# msp430_funky.net
KiCad netlist of a schematic drawn in EAGLE
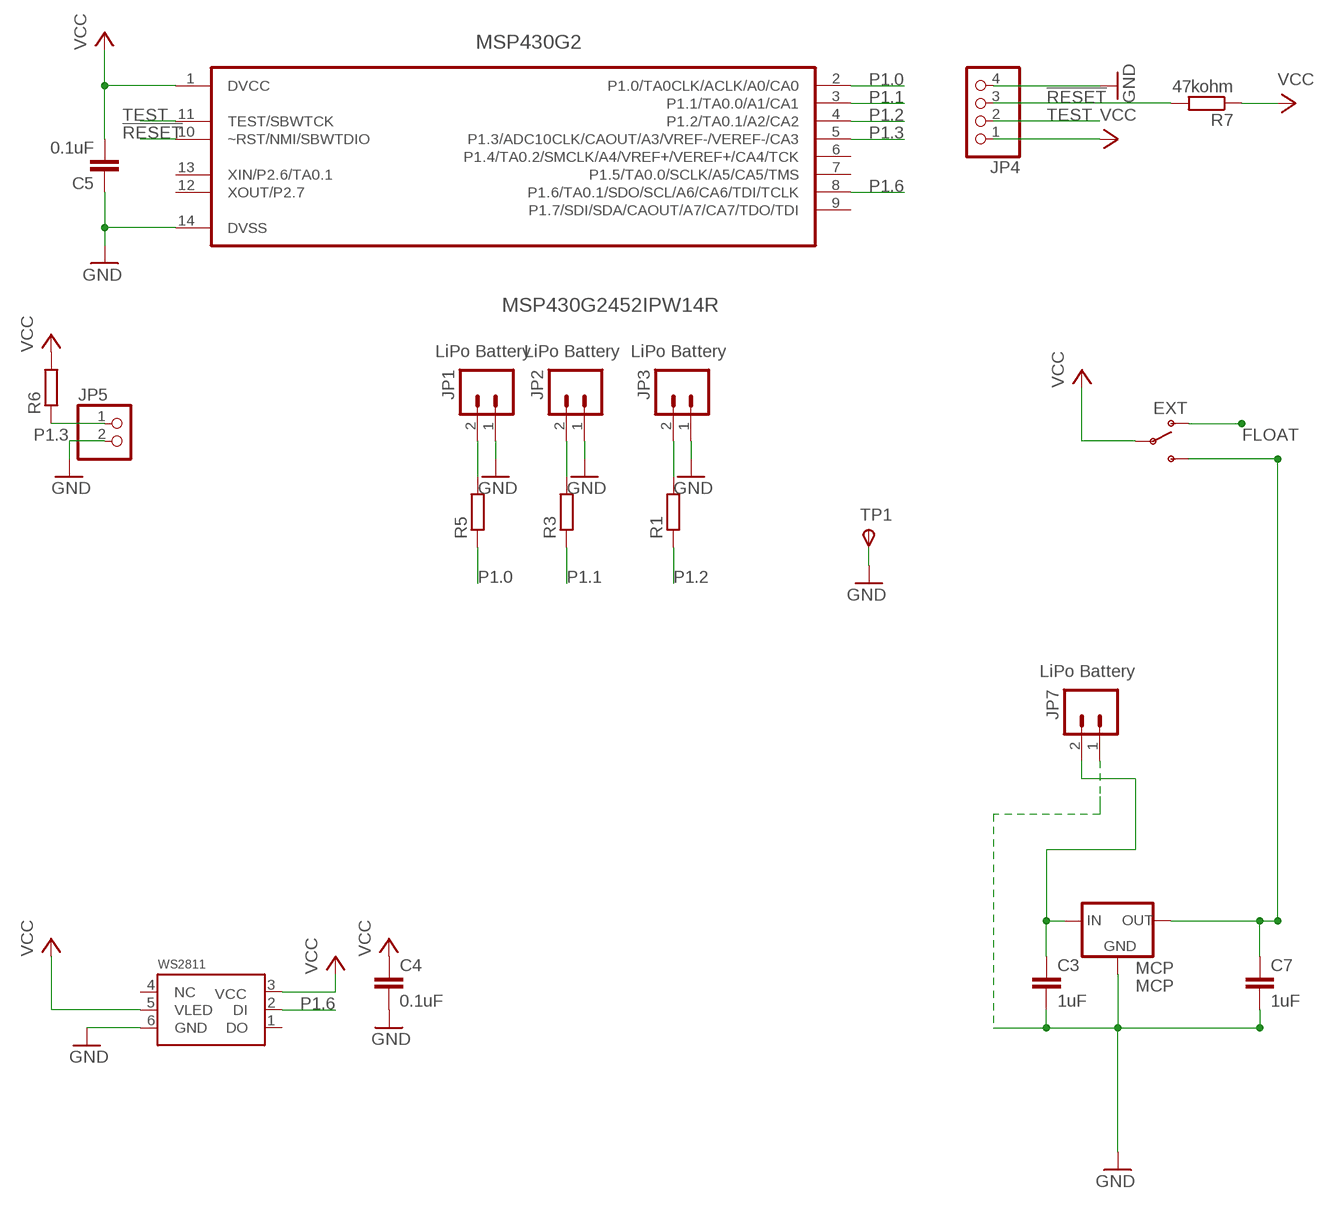
[diagram p0: schematic, sheet 1]

(export (version "E")
  (design (tool "Eeschema 10.0.6"))
  (components
    (comp (ref "C3")
      (value "1uF")
      (footprint "eagle-import:C0805")
      (libsource (lib "eagle-import") (part "C-EUC0805"))
    )
    (comp (ref "C4")
      (value "0.1uF")
      (footprint "eagle-import:C0805")
      (libsource (lib "eagle-import") (part "C-EUC0805"))
    )
    (comp (ref "C5")
      (value "0.1uF")
      (footprint "eagle-import:C0805")
      (libsource (lib "eagle-import") (part "C-EUC0805"))
    )
    (comp (ref "C7")
      (value "1uF")
      (footprint "eagle-import:C0805")
      (libsource (lib "eagle-import") (part "C-EUC0805"))
    )
    (comp (ref "JP1")
      (value "LiPo Battery")
      (footprint "eagle-import:JST-2-PTH")
      (libsource (lib "eagle-import") (part "M02JST-PTH-2"))
    )
    (comp (ref "JP2")
      (value "LiPo Battery")
      (footprint "eagle-import:JST-2-PTH")
      (libsource (lib "eagle-import") (part "M02JST-PTH-2"))
    )
    (comp (ref "JP3")
      (value "LiPo Battery")
      (footprint "eagle-import:JST-2-PTH")
      (libsource (lib "eagle-import") (part "M02JST-PTH-2"))
    )
    (comp (ref "JP4")
      (value "PINHD-1X4")
      (footprint "eagle-import:1X04")
      (libsource (lib "eagle-import") (part "PINHD-1X4"))
    )
    (comp (ref "JP5")
      (value "PINHD-1X2")
      (footprint "eagle-import:1X02")
      (libsource (lib "eagle-import") (part "PINHD-1X2"))
    )
    (comp (ref "JP7")
      (value "LiPo Battery")
      (footprint "eagle-import:JST-2-PTH")
      (libsource (lib "eagle-import") (part "M02JST-PTH-2"))
    )
    (comp (ref "MCP")
      (value "MCP")
      (footprint "eagle-import:SOT-23")
      (libsource (lib "eagle-import") (part "MCP1700SOT-23"))
    )
    (comp (ref "MSP430G2")
      (value "MSP430G2452IPW14R")
      (footprint "eagle-import:SOP65P640X120-14N")
      (libsource (lib "eagle-import") (part "MSP430G2452IPW14R"))
    )
    (comp (ref "ON")
      (value "EXT")
      (footprint "eagle-import:SWITCH-SPDT")
      (libsource (lib "eagle-import") (part "SWITCH-SPSTPTH"))
    )
    (comp (ref "R1")
      (value "R-EU_R0805")
      (footprint "eagle-import:R0805")
      (libsource (lib "eagle-import") (part "R-EU_R0805"))
    )
    (comp (ref "R3")
      (value "R-EU_R0805")
      (footprint "eagle-import:R0805")
      (libsource (lib "eagle-import") (part "R-EU_R0805"))
    )
    (comp (ref "R5")
      (value "R-EU_R0805")
      (footprint "eagle-import:R0805")
      (libsource (lib "eagle-import") (part "R-EU_R0805"))
    )
    (comp (ref "R6")
      (value "R-EU_R0805")
      (footprint "eagle-import:R0805")
      (libsource (lib "eagle-import") (part "R-EU_R0805"))
    )
    (comp (ref "R7")
      (value "47kohm")
      (footprint "eagle-import:R0805")
      (libsource (lib "eagle-import") (part "R-EU_R0805"))
    )
    (comp (ref "TP1")
      (value "TPSTP20R")
      (footprint "eagle-import:TP20R")
      (libsource (lib "eagle-import") (part "TPSTP20R"))
    )
    (comp (ref "WS2811")
      (value "5050WS2811W")
      (footprint "eagle-import:RGBLED5050W")
      (libsource (lib "eagle-import") (part "5050WS2811W"))
    )
  )
  (nets
    (net (code "1") (name "/FLOAT") (class "Default")
      (node (ref "ON") (pin "1") (pinfunction "O_1") (pintype "passive"))
    )
    (net (code "2") (name "/P1.0") (class "Default")
      (node (ref "MSP430G2") (pin "2") (pinfunction "P1.0/TA0CLK/ACLK/A0/CA0_2") (pintype "bidirectional"))
      (node (ref "R5") (pin "1") (pinfunction "1_1") (pintype "passive"))
    )
    (net (code "3") (name "/P1.1") (class "Default")
      (node (ref "MSP430G2") (pin "3") (pinfunction "P1.1/TA0.0/A1/CA1_3") (pintype "bidirectional"))
      (node (ref "R3") (pin "1") (pinfunction "1_1") (pintype "passive"))
    )
    (net (code "4") (name "/P1.2") (class "Default")
      (node (ref "MSP430G2") (pin "4") (pinfunction "P1.2/TA0.1/A2/CA2_4") (pintype "bidirectional"))
      (node (ref "R1") (pin "1") (pinfunction "1_1") (pintype "passive"))
    )
    (net (code "5") (name "/P1.3") (class "Default")
      (node (ref "JP5") (pin "1") (pinfunction "1_1") (pintype "passive"))
      (node (ref "MSP430G2") (pin "5") (pinfunction "P1.3/ADC10CLK/CAOUT/A3/VREF-/VEREF-/CA3_5") (pintype "bidirectional"))
      (node (ref "R6") (pin "1") (pinfunction "1_1") (pintype "passive"))
    )
    (net (code "6") (name "/P1.6") (class "Default")
      (node (ref "MSP430G2") (pin "8") (pinfunction "P1.6/TA0.1/SDO/SCL/A6/CA6/TDI/TCLK_8") (pintype "bidirectional"))
      (node (ref "WS2811") (pin "2") (pinfunction "DI_2") (pintype "bidirectional"))
    )
    (net (code "7") (name "/TEST") (class "Default")
      (node (ref "JP4") (pin "2") (pinfunction "2_2") (pintype "passive"))
      (node (ref "MSP430G2") (pin "11") (pinfunction "TEST/SBWTCK_11") (pintype "input"))
    )
    (net (code "8") (name "/~{RESET}") (class "Default")
      (node (ref "JP4") (pin "3") (pinfunction "3_3") (pintype "passive"))
      (node (ref "MSP430G2") (pin "10") (pinfunction "~{RST/NMI/SBWTDIO}_10") (pintype "input"))
      (node (ref "R7") (pin "2") (pinfunction "2_2") (pintype "passive"))
    )
    (net (code "9") (name "GND") (class "Default")
      (node (ref "C3") (pin "2") (pinfunction "2_2") (pintype "passive"))
      (node (ref "C4") (pin "2") (pinfunction "2_2") (pintype "passive"))
      (node (ref "C5") (pin "1") (pinfunction "1_1") (pintype "passive"))
      (node (ref "C7") (pin "2") (pinfunction "2_2") (pintype "passive"))
      (node (ref "JP1") (pin "1") (pinfunction "1_1") (pintype "passive"))
      (node (ref "JP2") (pin "1") (pinfunction "1_1") (pintype "passive"))
      (node (ref "JP3") (pin "1") (pinfunction "1_1") (pintype "passive"))
      (node (ref "JP4") (pin "4") (pinfunction "4_4") (pintype "passive"))
      (node (ref "JP5") (pin "2") (pinfunction "2_2") (pintype "passive"))
      (node (ref "JP7") (pin "1") (pinfunction "1_1") (pintype "passive"))
      (node (ref "MCP") (pin "1") (pinfunction "GND_1") (pintype "input"))
      (node (ref "MSP430G2") (pin "14") (pinfunction "DVSS_14") (pintype "power_in"))
      (node (ref "TP1") (pin "TP") (pinfunction "PP_TP") (pintype "input"))
      (node (ref "WS2811") (pin "6") (pinfunction "GND_6") (pintype "bidirectional"))
    )
    (net (code "10") (name "Net-(JP1-Pad2)") (class "Default")
      (node (ref "JP1") (pin "2") (pinfunction "2_2") (pintype "passive"))
      (node (ref "R5") (pin "2") (pinfunction "2_2") (pintype "passive"))
    )
    (net (code "11") (name "Net-(JP2-Pad2)") (class "Default")
      (node (ref "JP2") (pin "2") (pinfunction "2_2") (pintype "passive"))
      (node (ref "R3") (pin "2") (pinfunction "2_2") (pintype "passive"))
    )
    (net (code "12") (name "Net-(JP3-Pad2)") (class "Default")
      (node (ref "JP3") (pin "2") (pinfunction "2_2") (pintype "passive"))
      (node (ref "R1") (pin "2") (pinfunction "2_2") (pintype "passive"))
    )
    (net (code "13") (name "Net-(MCP-IN)") (class "Default")
      (node (ref "C3") (pin "1") (pinfunction "1_1") (pintype "passive"))
      (node (ref "JP7") (pin "2") (pinfunction "2_2") (pintype "passive"))
      (node (ref "MCP") (pin "3") (pinfunction "IN_3") (pintype "input"))
    )
    (net (code "14") (name "Net-(MCP-OUT)") (class "Default")
      (node (ref "C7") (pin "1") (pinfunction "1_1") (pintype "passive"))
      (node (ref "MCP") (pin "2") (pinfunction "OUT_2") (pintype "passive"))
      (node (ref "ON") (pin "3") (pinfunction "S_3") (pintype "passive"))
    )
    (net (code "15") (name "VCC") (class "Default")
      (node (ref "C4") (pin "1") (pinfunction "1_1") (pintype "passive"))
      (node (ref "C5") (pin "2") (pinfunction "2_2") (pintype "passive"))
      (node (ref "JP4") (pin "1") (pinfunction "1_1") (pintype "passive"))
      (node (ref "MSP430G2") (pin "1") (pinfunction "DVCC_1") (pintype "power_in"))
      (node (ref "ON") (pin "2") (pinfunction "P_2") (pintype "passive"))
      (node (ref "R6") (pin "2") (pinfunction "2_2") (pintype "passive"))
      (node (ref "R7") (pin "1") (pinfunction "1_1") (pintype "passive"))
      (node (ref "WS2811") (pin "3") (pinfunction "VCC_3") (pintype "bidirectional"))
      (node (ref "WS2811") (pin "5") (pinfunction "VLED_5") (pintype "bidirectional"))
    )
    (net (code "16") (name "unconnected-(MSP430G2-P1.4{slash}TA0.2{slash}SMCLK{slash}A4{slash}VREF+{slash}VEREF+{slash}CA4{slash}TCK-Pad6)") (class "Default")
      (node (ref "MSP430G2") (pin "6") (pinfunction "P1.4/TA0.2/SMCLK/A4/VREF+/VEREF+/CA4/TCK_6") (pintype "bidirectional"))
    )
    (net (code "17") (name "unconnected-(MSP430G2-P1.5{slash}TA0.0{slash}SCLK{slash}A5{slash}CA5{slash}TMS-Pad7)") (class "Default")
      (node (ref "MSP430G2") (pin "7") (pinfunction "P1.5/TA0.0/SCLK/A5/CA5/TMS_7") (pintype "bidirectional"))
    )
    (net (code "18") (name "unconnected-(MSP430G2-P1.7{slash}SDI{slash}SDA{slash}CAOUT{slash}A7{slash}CA7{slash}TDO{slash}TDI-Pad9)") (class "Default")
      (node (ref "MSP430G2") (pin "9") (pinfunction "P1.7/SDI/SDA/CAOUT/A7/CA7/TDO/TDI_9") (pintype "bidirectional"))
    )
    (net (code "19") (name "unconnected-(MSP430G2-XIN{slash}P2.6{slash}TA0.1-Pad13)") (class "Default")
      (node (ref "MSP430G2") (pin "13") (pinfunction "XIN/P2.6/TA0.1_13") (pintype "bidirectional"))
    )
    (net (code "20") (name "unconnected-(MSP430G2-XOUT{slash}P2.7-Pad12)") (class "Default")
      (node (ref "MSP430G2") (pin "12") (pinfunction "XOUT/P2.7_12") (pintype "bidirectional"))
    )
    (net (code "21") (name "unconnected-(WS2811-DO-Pad1)") (class "Default")
      (node (ref "WS2811") (pin "1") (pinfunction "DO_1") (pintype "bidirectional"))
    )
    (net (code "22") (name "unconnected-(WS2811-NC-Pad4)") (class "Default")
      (node (ref "WS2811") (pin "4") (pinfunction "NC_4") (pintype "bidirectional"))
    )
  )
)
